# schematic_diagram.net
KiCad netlist of a schematic drawn in EasyEDA
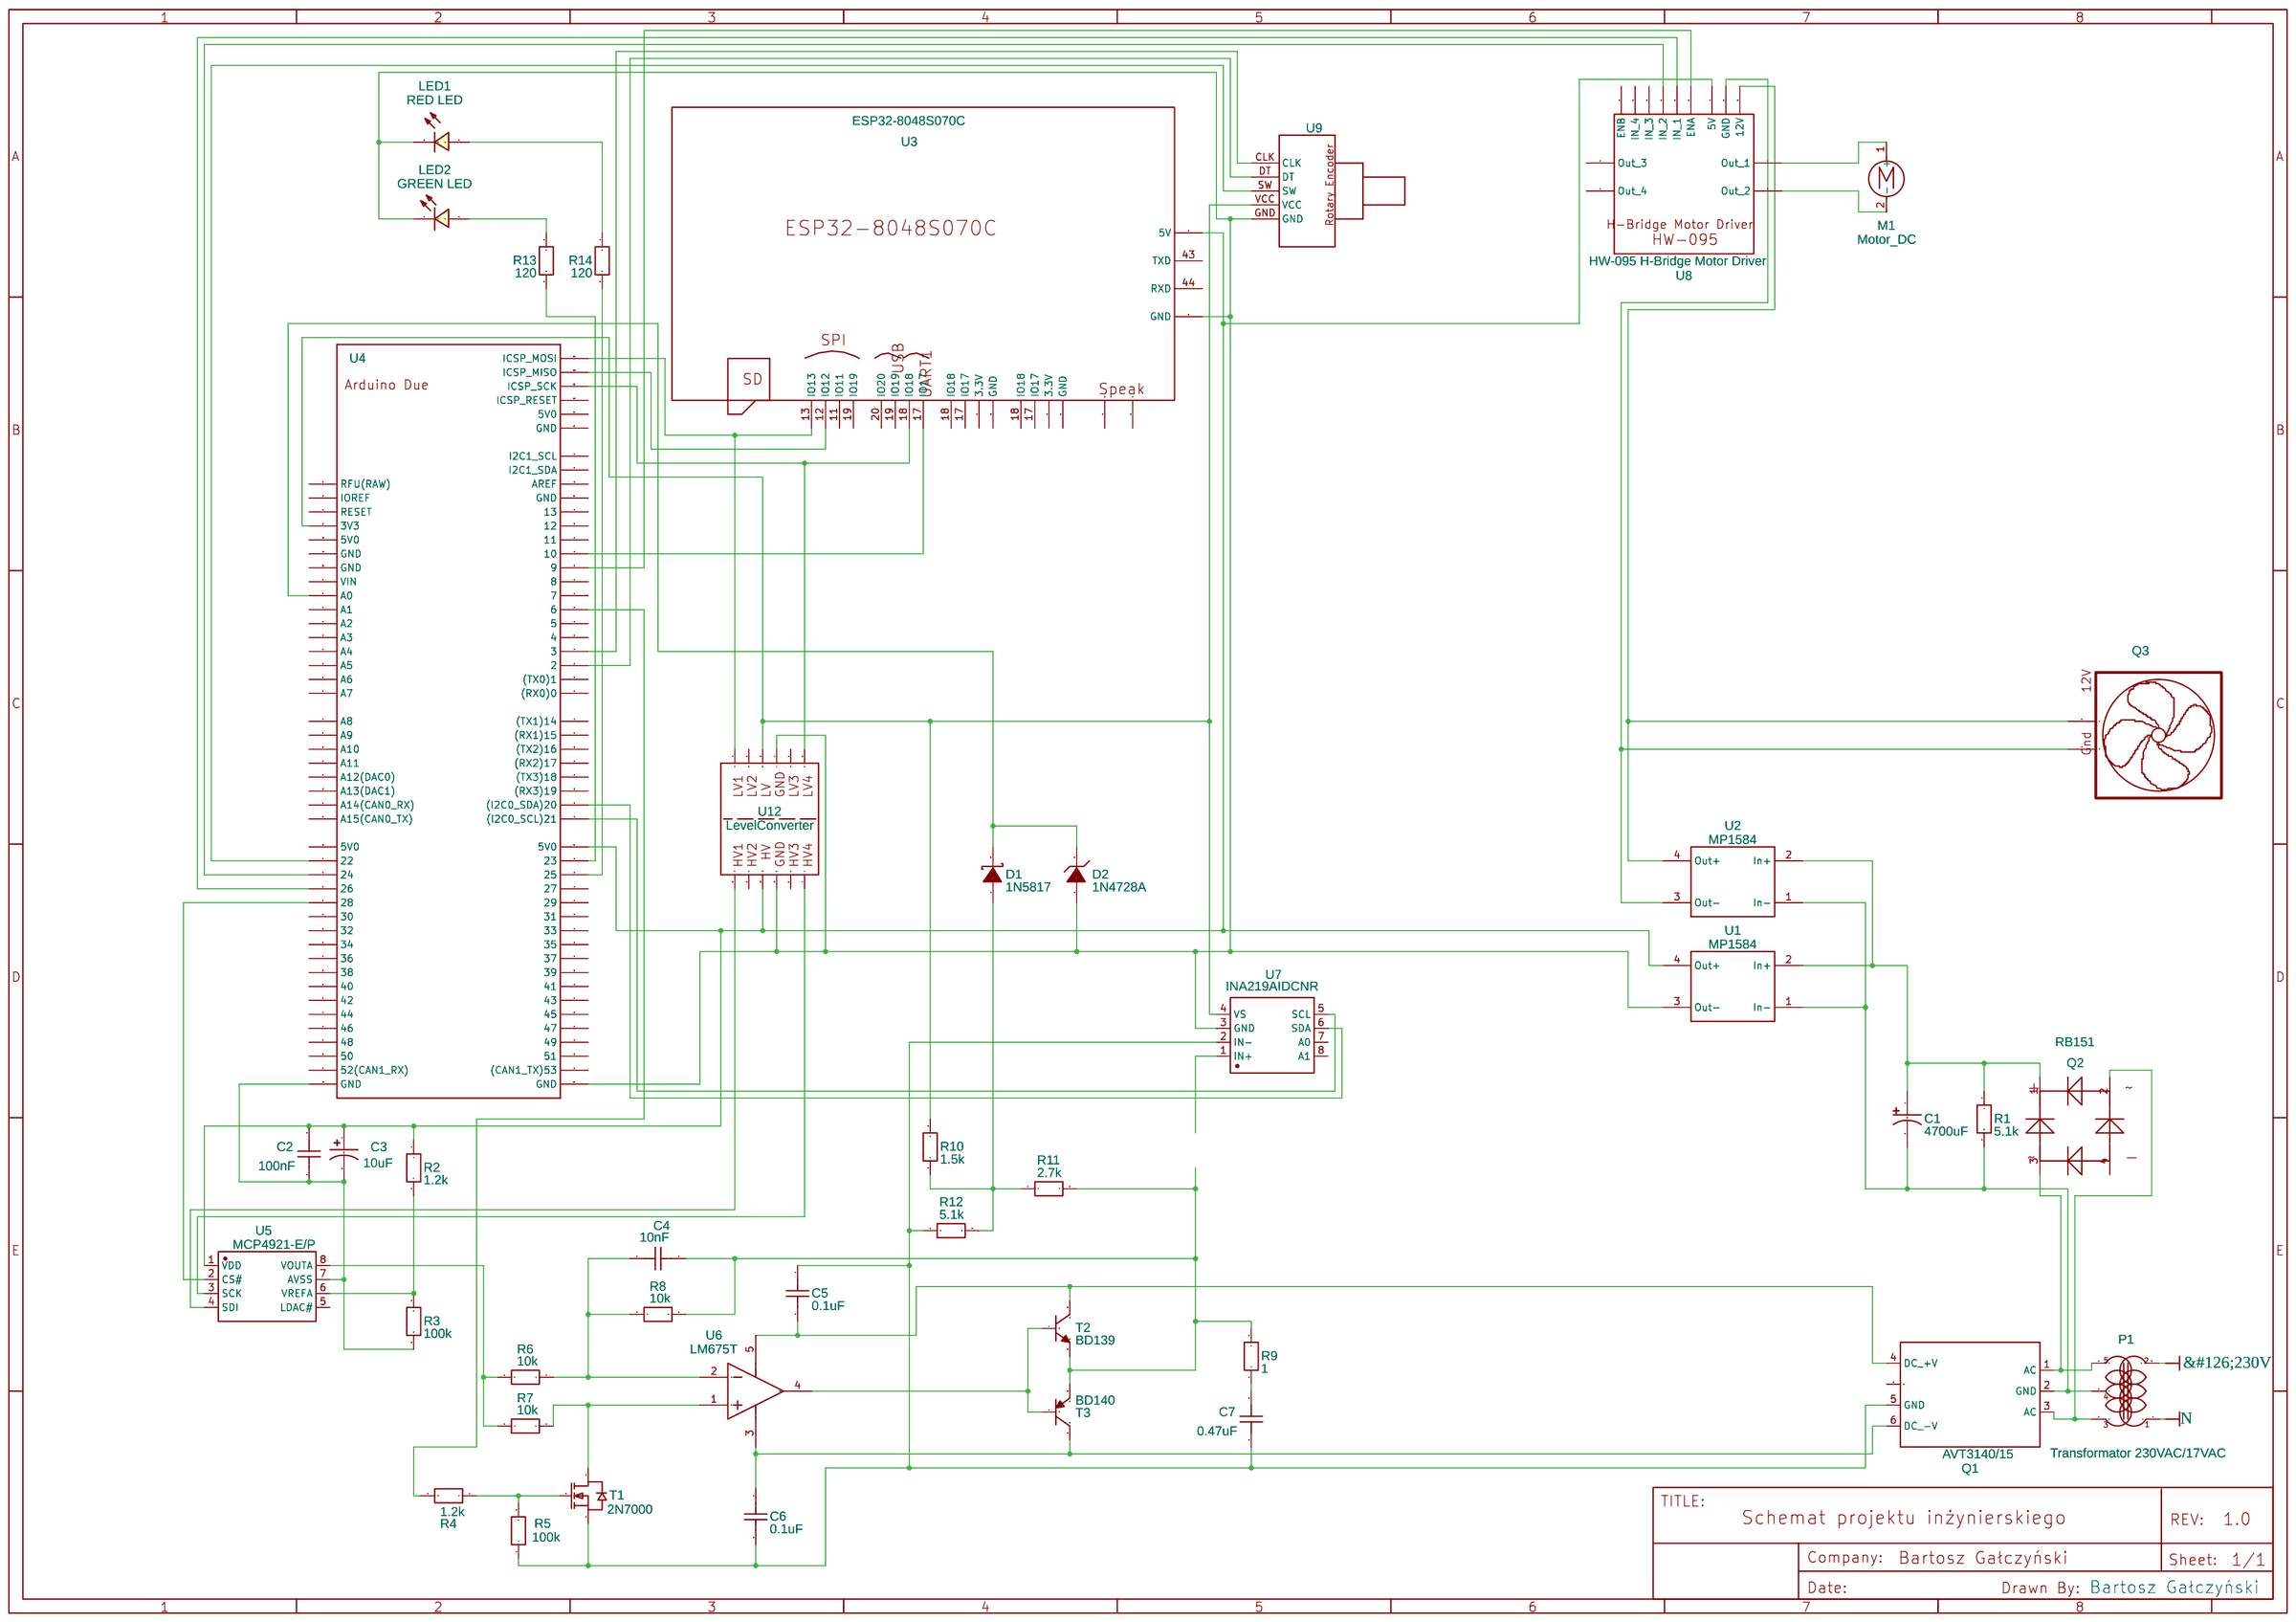
[diagram p0: schematic sheet]

(export (version "E")
  (design (tool "Eeschema 10.0.6"))
  (components
    (comp (ref "C1")
      (value "4700uF")
      (fields
        (field (name "Manufacturer Part") "50ZLH220MEFC10X16")
        (field (name "Manufacturer") "rubycon(红宝石)")
      )
      (libsource (lib "") (part "50ZLH220MEFC10X16"))
    )
    (comp (ref "C2") (value "100nF") (libsource (lib "") (part "C_0603_US_1")))
    (comp (ref "C3") (value "10uF") (libsource (lib "") (part "C_Tan_SMD_A_US")))
    (comp (ref "C4") (value "10nF") (libsource (lib "") (part "C_0603_US")))
    (comp (ref "C5") (value "0.1uF") (libsource (lib "") (part "C_0603_US_2")))
    (comp (ref "C6") (value "0.1uF") (libsource (lib "") (part "C_0603_US_2")))
    (comp (ref "C7") (value "0.47uF") (libsource (lib "") (part "C_0603_US_1")))
    (comp (ref "D1")
      (value "1N5817")
      (fields (field (name "Manufacturer") "MDD(辰达半导体)"))
      (libsource (lib "") (part "1N5817"))
    )
    (comp (ref "D2")
      (value "1N4728A")
      (fields (field (name "Manufacturer Part") "1N4733A") (field (name "Manufacturer") "TC(德昌)"))
      (libsource (lib "") (part "1N4733A"))
    )
    (comp (ref "LED1")
      (value "RED LED")
      (fields (field (name "Manufacturer Part") "LED05-红灯"))
      (libsource (lib "") (part "LED"))
    )
    (comp (ref "LED2")
      (value "GREEN LED")
      (fields (field (name "Manufacturer Part") "BLUEled-0603"))
      (libsource (lib "") (part "GREENLED-0603"))
    )
    (comp (ref "M1") (value "Motor_DC") (libsource (lib "") (part "Motor_DC")))
    (comp (ref "P1")
      (value "Transformator 230VAC/17VAC")
      (fields (field (name "Manufacturer Part") "Transformers"))
      (libsource (lib "") (part "TRANS_TOROIDE_40_20"))
    )
    (comp (ref "Q1")
      (value "AVT3140/15")
      (fields (field (name "Manufacturer Part") "SI7949DP-T1-GE3") (field (name "Manufacturer") "VISHAY(威世)"))
      (libsource (lib "") (part "POWER SUPPLY"))
    )
    (comp (ref "Q2")
      (value "RB151")
      (fields (field (name "Manufacturer Part") "RB151 THRU RB157"))
      (libsource (lib "") (part "SILICON BRIDGE RECTIFIER"))
    )
    (comp (ref "Q3") (value "NO") (libsource (lib "") (part "Fan12V")))
    (comp (ref "R1") (value "5.1k") (libsource (lib "") (part "R_0603_EU")))
    (comp (ref "R2") (value "1.2k") (libsource (lib "") (part "R_0603_EU")))
    (comp (ref "R3") (value "100k") (libsource (lib "") (part "R_0603_EU")))
    (comp (ref "R4") (value "1.2k") (libsource (lib "") (part "R_0603_EU_1")))
    (comp (ref "R5") (value "100k") (libsource (lib "") (part "R_0603_EU_3")))
    (comp (ref "R6") (value "10k") (libsource (lib "") (part "R_0603_EU_1")))
    (comp (ref "R7") (value "10k") (libsource (lib "") (part "R_0603_EU_1")))
    (comp (ref "R8") (value "10k") (libsource (lib "") (part "R_0603_EU_1")))
    (comp (ref "R9") (value "1") (libsource (lib "") (part "R_0603_EU")))
    (comp (ref "R10") (value "1.5k") (libsource (lib "") (part "R_0603_EU")))
    (comp (ref "R11") (value "2.7k") (libsource (lib "") (part "R_0603_EU_2")))
    (comp (ref "R12") (value "5.1k") (libsource (lib "") (part "R_0603_EU_2")))
    (comp (ref "R13") (value "120") (libsource (lib "") (part "R_0603_EU_3")))
    (comp (ref "R14") (value "120") (libsource (lib "") (part "R_0603_EU")))
    (comp (ref "T1")
      (value "2N7000")
      (fields (field (name "Manufacturer") "CJ(江苏长电/长晶)"))
      (libsource (lib "") (part "2N7000"))
    )
    (comp (ref "T2")
      (value "BD139")
      (fields (field (name "Manufacturer") "ST(意法半导体)"))
      (libsource (lib "") (part "BD139"))
    )
    (comp (ref "T3")
      (value "BD140")
      (fields (field (name "Manufacturer") "ST(意法半导体)"))
      (libsource (lib "") (part "BD140"))
    )
    (comp (ref "U1") (value "MP1584") (libsource (lib "") (part "MP1584")))
    (comp (ref "U2") (value "MP1584") (libsource (lib "") (part "MP1584")))
    (comp (ref "U3") (value "ESP32-8048S070C") (libsource (lib "") (part "ESP32-8048S070C")))
    (comp (ref "U4") (value "PA_DUE_BRD") (libsource (lib "") (part "PA_DUE_BRD")))
    (comp (ref "U5")
      (value "MCP4921-E/P")
      (fields (field (name "Manufacturer") "MICROCHIP(美国微芯)"))
      (libsource (lib "") (part "MCP4921-E/P"))
    )
    (comp (ref "U6")
      (value "LM675T")
      (fields (field (name "Manufacturer") "TI(德州仪器)"))
      (libsource (lib "") (part "LM675T"))
    )
    (comp (ref "U7")
      (value "INA219AIDCNR")
      (fields (field (name "Manufacturer") "TI(德州仪器)"))
      (libsource (lib "") (part "INA219AIDCNR"))
    )
    (comp (ref "U8")
      (value "HW-095 H-Bridge Motor Driver")
      (fields (field (name "Manufacturer Part") "HW-095") (field (name "Manufacturer") "Lafvin"))
      (libsource (lib "") (part "HW-095 H-Bridge Motor Driver"))
    )
    (comp (ref "U9") (value "NO") (libsource (lib "") (part "ROTARYENCODER")))
    (comp (ref "U12") (value "LevelConverter") (libsource (lib "") (part "LevelConverter_4")))
  )
  (nets
    (net (code "1") (name "&#126;230V") (class "Default")
      (node (ref "P1") (pin "2") (pinfunction "2_2") (pintype "unspecified"))
    )
    (net (code "2") (name "N") (class "Default")
      (node (ref "P1") (pin "1") (pinfunction "1_1") (pintype "unspecified"))
    )
    (net (code "3") (name "Net-(C7-Pad2)") (class "Default")
      (node (ref "C7") (pin "2") (pinfunction "2_2") (pintype "unspecified"))
      (node (ref "R9") (pin "2") (pinfunction "2_2") (pintype "unspecified"))
    )
    (net (code "4") (name "Net-(D1-A)") (class "Default")
      (node (ref "D1") (pin "1") (pinfunction "A_1") (pintype "unspecified"))
      (node (ref "R10") (pin "2") (pinfunction "2_2") (pintype "unspecified"))
      (node (ref "R11") (pin "1") (pinfunction "1_1") (pintype "unspecified"))
      (node (ref "R12") (pin "2") (pinfunction "2_2") (pintype "unspecified"))
    )
    (net (code "5") (name "Net-(D1-K)") (class "Default")
      (node (ref "D1") (pin "2") (pinfunction "K_2") (pintype "unspecified"))
      (node (ref "D2") (pin "2") (pinfunction "K_2") (pintype "unspecified"))
      (node (ref "U4") (pin "A0") (pinfunction "A0_A0") (pintype "unspecified"))
    )
    (net (code "6") (name "Net-(D2-A)") (class "Default")
      (node (ref "D2") (pin "1") (pinfunction "A_1") (pintype "unspecified"))
      (node (ref "LED1") (pin "2") (pinfunction "2_2") (pintype "unspecified"))
      (node (ref "LED2") (pin "1") (pinfunction "K_1") (pintype "unspecified"))
      (node (ref "U1") (pin "3") (pinfunction "Out-_3") (pintype "unspecified"))
      (node (ref "U12") (pin "4") (pinfunction "4_4") (pintype "input"))
      (node (ref "U12") (pin "9") (pinfunction "9_9") (pintype "input"))
      (node (ref "U3") (pin "GND") (pinfunction "GND_GND") (pintype "unspecified"))
      (node (ref "U4") (pin "GND@3") (pinfunction "GND_GND@3") (pintype "unspecified"))
      (node (ref "U7") (pin "3") (pinfunction "GND_3") (pintype "unspecified"))
      (node (ref "U9") (pin "GND") (pinfunction "GND_GND") (pintype "bidirectional"))
    )
    (net (code "7") (name "Net-(LED1-Pad1)") (class "Default")
      (node (ref "LED1") (pin "1") (pinfunction "1_1") (pintype "unspecified"))
      (node (ref "R14") (pin "1") (pinfunction "1_1") (pintype "unspecified"))
    )
    (net (code "8") (name "Net-(LED2-A)") (class "Default")
      (node (ref "LED2") (pin "2") (pinfunction "A_2") (pintype "unspecified"))
      (node (ref "R13") (pin "2") (pinfunction "2_2") (pintype "unspecified"))
    )
    (net (code "9") (name "Net-(M1-+)") (class "Default")
      (node (ref "M1") (pin "1") (pinfunction "+_1") (pintype "unspecified"))
      (node (ref "U8") (pin "1") (pinfunction "Out_1_1") (pintype "unspecified"))
    )
    (net (code "10") (name "Net-(M1--)") (class "Default")
      (node (ref "M1") (pin "2") (pinfunction "-_2") (pintype "unspecified"))
      (node (ref "U8") (pin "2") (pinfunction "Out_2_2") (pintype "unspecified"))
    )
    (net (code "11") (name "Net-(P1-Pad3)") (class "Default")
      (node (ref "P1") (pin "3") (pinfunction "3_3") (pintype "unspecified"))
      (node (ref "Q1") (pin "3") (pinfunction "AC_3") (pintype "passive"))
      (node (ref "Q2") (pin "2") (pinfunction "2_2") (pintype "unspecified"))
    )
    (net (code "12") (name "Net-(P1-Pad5)") (class "Default")
      (node (ref "P1") (pin "5") (pinfunction "5_5") (pintype "unspecified"))
      (node (ref "Q1") (pin "1") (pinfunction "AC_1") (pintype "passive"))
      (node (ref "Q2") (pin "3") (pinfunction "3_3") (pintype "unspecified"))
    )
    (net (code "13") (name "Net-(Q1-DC_+V)") (class "Default")
      (node (ref "C5") (pin "2") (pinfunction "2_2") (pintype "unspecified"))
      (node (ref "Q1") (pin "4") (pinfunction "DC_+V_4") (pintype "passive"))
      (node (ref "T2") (pin "2") (pinfunction "C_2") (pintype "unspecified"))
      (node (ref "U6") (pin "5") (pinfunction "VCC_5") (pintype "passive"))
    )
    (net (code "14") (name "Net-(Q1-DC_-V)") (class "Default")
      (node (ref "C6") (pin "1") (pinfunction "1_1") (pintype "unspecified"))
      (node (ref "Q1") (pin "6") (pinfunction "DC_-V_6") (pintype "passive"))
      (node (ref "T3") (pin "2") (pinfunction "C_2") (pintype "unspecified"))
      (node (ref "U6") (pin "3") (pinfunction "VEE_3") (pintype "passive"))
    )
    (net (code "15") (name "Net-(R4-Pad2)") (class "Default")
      (node (ref "R4") (pin "2") (pinfunction "2_2") (pintype "unspecified"))
      (node (ref "U4") (pin "6") (pinfunction "6_6") (pintype "unspecified"))
    )
    (net (code "16") (name "Net-(R13-Pad1)") (class "Default")
      (node (ref "R13") (pin "1") (pinfunction "1_1") (pintype "unspecified"))
      (node (ref "U4") (pin "23") (pinfunction "23_23") (pintype "unspecified"))
    )
    (net (code "17") (name "Net-(R14-Pad2)") (class "Default")
      (node (ref "R14") (pin "2") (pinfunction "2_2") (pintype "unspecified"))
      (node (ref "U4") (pin "25") (pinfunction "25_25") (pintype "unspecified"))
    )
    (net (code "18") (name "Net-(T1-D)") (class "Default")
      (node (ref "R7") (pin "1") (pinfunction "1_1") (pintype "unspecified"))
      (node (ref "T1") (pin "3") (pinfunction "D_3") (pintype "unspecified"))
      (node (ref "U6") (pin "1") (pinfunction "+IN_1") (pintype "unspecified"))
    )
    (net (code "19") (name "Net-(T1-G)") (class "Default")
      (node (ref "R4") (pin "1") (pinfunction "1_1") (pintype "unspecified"))
      (node (ref "R5") (pin "2") (pinfunction "2_2") (pintype "unspecified"))
      (node (ref "T1") (pin "2") (pinfunction "G_2") (pintype "unspecified"))
    )
    (net (code "20") (name "Net-(T1-S)") (class "Default")
      (node (ref "C5") (pin "1") (pinfunction "1_1") (pintype "unspecified"))
      (node (ref "C6") (pin "2") (pinfunction "2_2") (pintype "unspecified"))
      (node (ref "C7") (pin "1") (pinfunction "1_1") (pintype "unspecified"))
      (node (ref "Q1") (pin "5") (pinfunction "GND_5") (pintype "passive"))
      (node (ref "R12") (pin "1") (pinfunction "1_1") (pintype "unspecified"))
      (node (ref "R5") (pin "1") (pinfunction "1_1") (pintype "unspecified"))
      (node (ref "T1") (pin "1") (pinfunction "S_1") (pintype "unspecified"))
      (node (ref "U7") (pin "2") (pinfunction "IN-_2") (pintype "unspecified"))
    )
    (net (code "21") (name "Net-(T2-B)") (class "Default")
      (node (ref "T2") (pin "1") (pinfunction "B_1") (pintype "unspecified"))
      (node (ref "T3") (pin "1") (pinfunction "B_1") (pintype "unspecified"))
      (node (ref "U6") (pin "4") (pinfunction "OUT_4") (pintype "output"))
    )
    (net (code "22") (name "Net-(T2-E)") (class "Default")
      (node (ref "C4") (pin "2") (pinfunction "2_2") (pintype "unspecified"))
      (node (ref "R11") (pin "2") (pinfunction "2_2") (pintype "unspecified"))
      (node (ref "R8") (pin "1") (pinfunction "1_1") (pintype "unspecified"))
      (node (ref "R9") (pin "1") (pinfunction "1_1") (pintype "unspecified"))
      (node (ref "T2") (pin "3") (pinfunction "E_3") (pintype "unspecified"))
      (node (ref "T3") (pin "3") (pinfunction "E_3") (pintype "unspecified"))
    )
    (net (code "23") (name "Net-(U1-In+)") (class "Default")
      (node (ref "C1") (pin "1") (pinfunction "1_1") (pintype "unspecified"))
      (node (ref "Q2") (pin "1") (pinfunction "1_1") (pintype "unspecified"))
      (node (ref "R1") (pin "1") (pinfunction "1_1") (pintype "unspecified"))
      (node (ref "U1") (pin "2") (pinfunction "In+_2") (pintype "unspecified"))
      (node (ref "U2") (pin "2") (pinfunction "In+_2") (pintype "unspecified"))
    )
    (net (code "24") (name "Net-(U1-In-)") (class "Default")
      (node (ref "C1") (pin "2") (pinfunction "2_2") (pintype "unspecified"))
      (node (ref "P1") (pin "4") (pinfunction "4_4") (pintype "unspecified"))
      (node (ref "Q1") (pin "2") (pinfunction "GND_2") (pintype "passive"))
      (node (ref "R1") (pin "2") (pinfunction "2_2") (pintype "unspecified"))
      (node (ref "U1") (pin "1") (pinfunction "In-_1") (pintype "unspecified"))
      (node (ref "U2") (pin "1") (pinfunction "In-_1") (pintype "unspecified"))
    )
    (net (code "25") (name "Net-(U1-Out+)") (class "Default")
      (node (ref "C2") (pin "2") (pinfunction "2_2") (pintype "unspecified"))
      (node (ref "C3") (pin "1") (pinfunction "1_1") (pintype "unspecified"))
      (node (ref "R2") (pin "1") (pinfunction "1_1") (pintype "unspecified"))
      (node (ref "U1") (pin "4") (pinfunction "Out+_4") (pintype "unspecified"))
      (node (ref "U12") (pin "10") (pinfunction "10_10") (pintype "input"))
      (node (ref "U3") (pin "5V") (pinfunction "5V_5V") (pintype "unspecified"))
      (node (ref "U4") (pin "5V0@1") (pinfunction "5V0_5V0@1") (pintype "unspecified"))
      (node (ref "U5") (pin "1") (pinfunction "VDD_1") (pintype "unspecified"))
      (node (ref "U8") (pin "7") (pinfunction "5V_7") (pintype "unspecified"))
    )
    (net (code "26") (name "Net-(U2-Out+)") (class "Default")
      (node (ref "Q3") (pin "1") (pinfunction "1_1") (pintype "unspecified"))
      (node (ref "U2") (pin "4") (pinfunction "Out+_4") (pintype "unspecified"))
      (node (ref "U8") (pin "5") (pinfunction "12V_5") (pintype "unspecified"))
    )
    (net (code "27") (name "Net-(U2-Out-)") (class "Default")
      (node (ref "Q3") (pin "2") (pinfunction "2_2") (pintype "unspecified"))
      (node (ref "U2") (pin "3") (pinfunction "Out-_3") (pintype "unspecified"))
      (node (ref "U8") (pin "6") (pinfunction "GND_6") (pintype "unspecified"))
    )
    (net (code "28") (name "Net-(U3-IO12)") (class "Default")
      (node (ref "U3") (pin "12") (pinfunction "IO12_12") (pintype "unspecified"))
      (node (ref "U4") (pin "ICSP_MISO") (pinfunction "ICSP_MISO_ICSP_MISO") (pintype "unspecified"))
    )
    (net (code "29") (name "Net-(U3-IO13)") (class "Default")
      (node (ref "U12") (pin "1") (pinfunction "1_1") (pintype "input"))
      (node (ref "U3") (pin "13") (pinfunction "IO13_13") (pintype "unspecified"))
      (node (ref "U4") (pin "ICSP_MOSI") (pinfunction "ICSP_MOSI_ICSP_MOSI") (pintype "unspecified"))
    )
    (net (code "30") (name "Net-(U3-IO17)_1") (class "Default")
      (node (ref "U3") (pin "17") (pinfunction "IO17_17") (pintype "unspecified"))
      (node (ref "U4") (pin "10") (pinfunction "10_10") (pintype "unspecified"))
    )
    (net (code "31") (name "Net-(U3-IO18)_1") (class "Default")
      (node (ref "U12") (pin "6") (pinfunction "6_6") (pintype "input"))
      (node (ref "U3") (pin "18") (pinfunction "IO18_18") (pintype "unspecified"))
      (node (ref "U4") (pin "ICSP_SCK") (pinfunction "ICSP_SCK_ICSP_SCK") (pintype "unspecified"))
    )
    (net (code "32") (name "Net-(U4-(I2C0_SCL)21)") (class "Default")
      (node (ref "U4") (pin "21") (pinfunction "(I2C0_SCL)21_21") (pintype "unspecified"))
      (node (ref "U7") (pin "5") (pinfunction "SCL_5") (pintype "unspecified"))
    )
    (net (code "33") (name "Net-(U4-(I2C0_SDA)20)") (class "Default")
      (node (ref "U4") (pin "20") (pinfunction "(I2C0_SDA)20_20") (pintype "unspecified"))
      (node (ref "U7") (pin "6") (pinfunction "SDA_6") (pintype "unspecified"))
    )
    (net (code "34") (name "Net-(U4-Pad2)") (class "Default")
      (node (ref "U4") (pin "2") (pinfunction "2_2") (pintype "unspecified"))
      (node (ref "U9") (pin "DT") (pinfunction "DT_DT") (pintype "bidirectional"))
    )
    (net (code "35") (name "Net-(U4-Pad3)") (class "Default")
      (node (ref "U4") (pin "3") (pinfunction "3_3") (pintype "unspecified"))
      (node (ref "U9") (pin "CLK") (pinfunction "CLK_CLK") (pintype "bidirectional"))
    )
    (net (code "36") (name "Net-(U4-Pad22)") (class "Default")
      (node (ref "U4") (pin "22") (pinfunction "22_22") (pintype "unspecified"))
      (node (ref "U9") (pin "SW") (pinfunction "SW_SW") (pintype "bidirectional"))
    )
    (net (code "37") (name "Net-(U5-AVSS)") (class "Default")
      (node (ref "C2") (pin "1") (pinfunction "1_1") (pintype "unspecified"))
      (node (ref "C3") (pin "2") (pinfunction "2_2") (pintype "unspecified"))
      (node (ref "R3") (pin "2") (pinfunction "2_2") (pintype "unspecified"))
      (node (ref "U4") (pin "GND@2") (pinfunction "GND_GND@2") (pintype "unspecified"))
      (node (ref "U5") (pin "7") (pinfunction "AVSS_7") (pintype "unspecified"))
    )
    (net (code "38") (name "Net-(U5-CS#)") (class "Default")
      (node (ref "U4") (pin "28") (pinfunction "28_28") (pintype "unspecified"))
      (node (ref "U5") (pin "2") (pinfunction "CS#_2") (pintype "unspecified"))
    )
    (net (code "39") (name "Net-(U5-SCK)") (class "Default")
      (node (ref "U12") (pin "7") (pinfunction "7_7") (pintype "input"))
      (node (ref "U5") (pin "3") (pinfunction "SCK_3") (pintype "unspecified"))
    )
    (net (code "40") (name "Net-(U5-SDI)") (class "Default")
      (node (ref "U12") (pin "12") (pinfunction "12_12") (pintype "input"))
      (node (ref "U5") (pin "4") (pinfunction "SDI_4") (pintype "unspecified"))
    )
    (net (code "41") (name "Net-(U5-VOUTA)") (class "Default")
      (node (ref "R6") (pin "2") (pinfunction "2_2") (pintype "unspecified"))
      (node (ref "R7") (pin "2") (pinfunction "2_2") (pintype "unspecified"))
      (node (ref "U5") (pin "8") (pinfunction "VOUTA_8") (pintype "unspecified"))
    )
    (net (code "42") (name "Net-(U5-VREFA)") (class "Default")
      (node (ref "R2") (pin "2") (pinfunction "2_2") (pintype "unspecified"))
      (node (ref "R3") (pin "1") (pinfunction "1_1") (pintype "unspecified"))
      (node (ref "U5") (pin "6") (pinfunction "VREFA_6") (pintype "unspecified"))
    )
    (net (code "43") (name "Net-(U6--IN)") (class "Default")
      (node (ref "C4") (pin "1") (pinfunction "1_1") (pintype "unspecified"))
      (node (ref "R6") (pin "1") (pinfunction "1_1") (pintype "unspecified"))
      (node (ref "R8") (pin "2") (pinfunction "2_2") (pintype "unspecified"))
      (node (ref "U6") (pin "2") (pinfunction "-IN_2") (pintype "unspecified"))
    )
    (net (code "44") (name "Net-(U7-VS)") (class "Default")
      (node (ref "R10") (pin "1") (pinfunction "1_1") (pintype "unspecified"))
      (node (ref "U12") (pin "3") (pinfunction "3_3") (pintype "input"))
      (node (ref "U4") (pin "3V3") (pinfunction "3V3_3V3") (pintype "unspecified"))
      (node (ref "U7") (pin "4") (pinfunction "VS_4") (pintype "unspecified"))
      (node (ref "U9") (pin "VCC") (pinfunction "VCC_VCC") (pintype "bidirectional"))
    )
    (net (code "45") (name "Net-(U8-ENA)") (class "Default")
      (node (ref "U4") (pin "9") (pinfunction "9_9") (pintype "unspecified"))
      (node (ref "U8") (pin "8") (pinfunction "ENA_8") (pintype "unspecified"))
    )
    (net (code "46") (name "Net-(U8-IN_1)") (class "Default")
      (node (ref "U4") (pin "26") (pinfunction "26_26") (pintype "unspecified"))
      (node (ref "U8") (pin "9") (pinfunction "IN_1_9") (pintype "unspecified"))
    )
    (net (code "47") (name "Net-(U8-IN_2)") (class "Default")
      (node (ref "U4") (pin "24") (pinfunction "24_24") (pintype "unspecified"))
      (node (ref "U8") (pin "10") (pinfunction "IN_2_10") (pintype "unspecified"))
    )
    (net (code "48") (name "unconnected-(Q1-GND-Pad5)") (class "Default")
      (node (ref "Q1") (pin "5") (pinfunction "GND_5") (pintype "unspecified"))
    )
    (net (code "49") (name "unconnected-(Q2-Pad4)") (class "Default")
      (node (ref "Q2") (pin "4") (pinfunction "4_4") (pintype "unspecified"))
    )
    (net (code "50") (name "unconnected-(U3-5V-Pad5)") (class "Default")
      (node (ref "U3") (pin "5") (pinfunction "5V_5") (pintype "unspecified"))
    )
    (net (code "51") (name "unconnected-(U3-IO11-Pad11)") (class "Default")
      (node (ref "U3") (pin "11") (pinfunction "IO11_11") (pintype "unspecified"))
    )
    (net (code "52") (name "unconnected-(U3-IO17-Pad17)") (class "Default")
      (node (ref "U3") (pin "17") (pinfunction "IO17_17") (pintype "unspecified"))
    )
    (net (code "53") (name "unconnected-(U3-IO17-Pad17)_2") (class "Default")
      (node (ref "U3") (pin "17") (pinfunction "IO17_17") (pintype "unspecified"))
    )
    (net (code "54") (name "unconnected-(U3-IO18-Pad18)") (class "Default")
      (node (ref "U3") (pin "18") (pinfunction "IO18_18") (pintype "unspecified"))
    )
    (net (code "55") (name "unconnected-(U3-IO18-Pad18)_2") (class "Default")
      (node (ref "U3") (pin "18") (pinfunction "IO18_18") (pintype "unspecified"))
    )
    (net (code "56") (name "unconnected-(U3-IO19-Pad19)") (class "Default")
      (node (ref "U3") (pin "19") (pinfunction "IO19_19") (pintype "unspecified"))
    )
    (net (code "57") (name "unconnected-(U3-IO19-Pad19)_1") (class "Default")
      (node (ref "U3") (pin "19") (pinfunction "IO19_19") (pintype "unspecified"))
    )
    (net (code "58") (name "unconnected-(U3-IO20-Pad20)") (class "Default")
      (node (ref "U3") (pin "20") (pinfunction "IO20_20") (pintype "unspecified"))
    )
    (net (code "59") (name "unconnected-(U3-Pad3.3V)") (class "Default")
      (node (ref "U3") (pin "3.3V") (pinfunction "3.3V_3.3V") (pintype "unspecified"))
    )
    (net (code "60") (name "unconnected-(U3-Pad3.3V)_1") (class "Default")
      (node (ref "U3") (pin "3.3V") (pinfunction "3.3V_3.3V") (pintype "unspecified"))
    )
    (net (code "61") (name "unconnected-(U3-PadGND)") (class "Default")
      (node (ref "U3") (pin "GND") (pinfunction "GND_GND") (pintype "unspecified"))
    )
    (net (code "62") (name "unconnected-(U3-PadGND)_1") (class "Default")
      (node (ref "U3") (pin "GND") (pinfunction "GND_GND") (pintype "unspecified"))
    )
    (net (code "63") (name "unconnected-(U3-RXD-Pad44)") (class "Default")
      (node (ref "U3") (pin "44") (pinfunction "RXD_44") (pintype "unspecified"))
    )
    (net (code "64") (name "unconnected-(U3-TXD-Pad6)") (class "Default")
      (node (ref "U3") (pin "6") (pinfunction "TXD_6") (pintype "unspecified"))
    )
    (net (code "65") (name "unconnected-(U3-TXD-Pad43)") (class "Default")
      (node (ref "U3") (pin "43") (pinfunction "TXD_43") (pintype "unspecified"))
    )
    (net (code "66") (name "unconnected-(U4-(CAN1_TX)53-Pad53)") (class "Default")
      (node (ref "U4") (pin "53") (pinfunction "(CAN1_TX)53_53") (pintype "unspecified"))
    )
    (net (code "67") (name "unconnected-(U4-(RX0)0-Pad0)") (class "Default")
      (node (ref "U4") (pin "0") (pinfunction "(RX0)0_0") (pintype "unspecified"))
    )
    (net (code "68") (name "unconnected-(U4-(RX1)15-Pad15)") (class "Default")
      (node (ref "U4") (pin "15") (pinfunction "(RX1)15_15") (pintype "unspecified"))
    )
    (net (code "69") (name "unconnected-(U4-(RX2)17-Pad17)") (class "Default")
      (node (ref "U4") (pin "17") (pinfunction "(RX2)17_17") (pintype "unspecified"))
    )
    (net (code "70") (name "unconnected-(U4-(RX3)19-Pad19)") (class "Default")
      (node (ref "U4") (pin "19") (pinfunction "(RX3)19_19") (pintype "unspecified"))
    )
    (net (code "71") (name "unconnected-(U4-(TX0)1-Pad1)") (class "Default")
      (node (ref "U4") (pin "1") (pinfunction "(TX0)1_1") (pintype "unspecified"))
    )
    (net (code "72") (name "unconnected-(U4-(TX1)14-Pad14)") (class "Default")
      (node (ref "U4") (pin "14") (pinfunction "(TX1)14_14") (pintype "unspecified"))
    )
    (net (code "73") (name "unconnected-(U4-(TX2)16-Pad16)") (class "Default")
      (node (ref "U4") (pin "16") (pinfunction "(TX2)16_16") (pintype "unspecified"))
    )
    (net (code "74") (name "unconnected-(U4-(TX3)18-Pad18)") (class "Default")
      (node (ref "U4") (pin "18") (pinfunction "(TX3)18_18") (pintype "unspecified"))
    )
    (net (code "75") (name "unconnected-(U4-5V0-Pad5V0@0)") (class "Default")
      (node (ref "U4") (pin "5V0@0") (pinfunction "5V0_5V0@0") (pintype "unspecified"))
    )
    (net (code "76") (name "unconnected-(U4-5V0-Pad5V0@2)") (class "Default")
      (node (ref "U4") (pin "5V0@2") (pinfunction "5V0_5V0@2") (pintype "unspecified"))
    )
    (net (code "77") (name "unconnected-(U4-5V0-Pad5V0@3)") (class "Default")
      (node (ref "U4") (pin "5V0@3") (pinfunction "5V0_5V0@3") (pintype "passive"))
    )
    (net (code "78") (name "unconnected-(U4-52(CAN1_RX)-Pad52)") (class "Default")
      (node (ref "U4") (pin "52") (pinfunction "52(CAN1_RX)_52") (pintype "unspecified"))
    )
    (net (code "79") (name "unconnected-(U4-A12(DAC0)-PadA12)") (class "Default")
      (node (ref "U4") (pin "A12") (pinfunction "A12(DAC0)_A12") (pintype "unspecified"))
    )
    (net (code "80") (name "unconnected-(U4-A13(DAC1)-PadA13)") (class "Default")
      (node (ref "U4") (pin "A13") (pinfunction "A13(DAC1)_A13") (pintype "unspecified"))
    )
    (net (code "81") (name "unconnected-(U4-A14(CAN0_RX)-PadA14)") (class "Default")
      (node (ref "U4") (pin "A14") (pinfunction "A14(CAN0_RX)_A14") (pintype "unspecified"))
    )
    (net (code "82") (name "unconnected-(U4-A15(CAN0_TX)-PadA15)") (class "Default")
      (node (ref "U4") (pin "A15") (pinfunction "A15(CAN0_TX)_A15") (pintype "unspecified"))
    )
    (net (code "83") (name "unconnected-(U4-GND-PadGND@0)") (class "Default")
      (node (ref "U4") (pin "GND@0") (pinfunction "GND_GND@0") (pintype "unspecified"))
    )
    (net (code "84") (name "unconnected-(U4-GND-PadGND@1)") (class "Default")
      (node (ref "U4") (pin "GND@1") (pinfunction "GND_GND@1") (pintype "unspecified"))
    )
    (net (code "85") (name "unconnected-(U4-GND-PadGND@4)") (class "Default")
      (node (ref "U4") (pin "GND@4") (pinfunction "GND_GND@4") (pintype "unspecified"))
    )
    (net (code "86") (name "unconnected-(U4-GND-PadGND@5)") (class "Default")
      (node (ref "U4") (pin "GND@5") (pinfunction "GND_GND@5") (pintype "passive"))
    )
    (net (code "87") (name "unconnected-(U4-I2C1_SCL-PadSCL1)") (class "Default")
      (node (ref "U4") (pin "SCL1") (pinfunction "I2C1_SCL_SCL1") (pintype "unspecified"))
    )
    (net (code "88") (name "unconnected-(U4-I2C1_SDA-PadSDA1)") (class "Default")
      (node (ref "U4") (pin "SDA1") (pinfunction "I2C1_SDA_SDA1") (pintype "unspecified"))
    )
    (net (code "89") (name "unconnected-(U4-Pad4)") (class "Default")
      (node (ref "U4") (pin "4") (pinfunction "4_4") (pintype "unspecified"))
    )
    (net (code "90") (name "unconnected-(U4-Pad5)") (class "Default")
      (node (ref "U4") (pin "5") (pinfunction "5_5") (pintype "unspecified"))
    )
    (net (code "91") (name "unconnected-(U4-Pad7)") (class "Default")
      (node (ref "U4") (pin "7") (pinfunction "7_7") (pintype "unspecified"))
    )
    (net (code "92") (name "unconnected-(U4-Pad8)") (class "Default")
      (node (ref "U4") (pin "8") (pinfunction "8_8") (pintype "unspecified"))
    )
    (net (code "93") (name "unconnected-(U4-Pad11)") (class "Default")
      (node (ref "U4") (pin "11") (pinfunction "11_11") (pintype "unspecified"))
    )
    (net (code "94") (name "unconnected-(U4-Pad12)") (class "Default")
      (node (ref "U4") (pin "12") (pinfunction "12_12") (pintype "unspecified"))
    )
    (net (code "95") (name "unconnected-(U4-Pad13)") (class "Default")
      (node (ref "U4") (pin "13") (pinfunction "13_13") (pintype "unspecified"))
    )
    (net (code "96") (name "unconnected-(U4-Pad27)") (class "Default")
      (node (ref "U4") (pin "27") (pinfunction "27_27") (pintype "unspecified"))
    )
    (net (code "97") (name "unconnected-(U4-Pad29)") (class "Default")
      (node (ref "U4") (pin "29") (pinfunction "29_29") (pintype "unspecified"))
    )
    (net (code "98") (name "unconnected-(U4-Pad30)") (class "Default")
      (node (ref "U4") (pin "30") (pinfunction "30_30") (pintype "unspecified"))
    )
    (net (code "99") (name "unconnected-(U4-Pad31)") (class "Default")
      (node (ref "U4") (pin "31") (pinfunction "31_31") (pintype "unspecified"))
    )
    (net (code "100") (name "unconnected-(U4-Pad32)") (class "Default")
      (node (ref "U4") (pin "32") (pinfunction "32_32") (pintype "unspecified"))
    )
    (net (code "101") (name "unconnected-(U4-Pad33)") (class "Default")
      (node (ref "U4") (pin "33") (pinfunction "33_33") (pintype "unspecified"))
    )
    (net (code "102") (name "unconnected-(U4-Pad34)") (class "Default")
      (node (ref "U4") (pin "34") (pinfunction "34_34") (pintype "unspecified"))
    )
    (net (code "103") (name "unconnected-(U4-Pad35)") (class "Default")
      (node (ref "U4") (pin "35") (pinfunction "35_35") (pintype "unspecified"))
    )
    (net (code "104") (name "unconnected-(U4-Pad36)") (class "Default")
      (node (ref "U4") (pin "36") (pinfunction "36_36") (pintype "unspecified"))
    )
    (net (code "105") (name "unconnected-(U4-Pad37)") (class "Default")
      (node (ref "U4") (pin "37") (pinfunction "37_37") (pintype "unspecified"))
    )
    (net (code "106") (name "unconnected-(U4-Pad38)") (class "Default")
      (node (ref "U4") (pin "38") (pinfunction "38_38") (pintype "unspecified"))
    )
    (net (code "107") (name "unconnected-(U4-Pad39)") (class "Default")
      (node (ref "U4") (pin "39") (pinfunction "39_39") (pintype "unspecified"))
    )
    (net (code "108") (name "unconnected-(U4-Pad40)") (class "Default")
      (node (ref "U4") (pin "40") (pinfunction "40_40") (pintype "unspecified"))
    )
    (net (code "109") (name "unconnected-(U4-Pad41)") (class "Default")
      (node (ref "U4") (pin "41") (pinfunction "41_41") (pintype "unspecified"))
    )
    (net (code "110") (name "unconnected-(U4-Pad42)") (class "Default")
      (node (ref "U4") (pin "42") (pinfunction "42_42") (pintype "unspecified"))
    )
    (net (code "111") (name "unconnected-(U4-Pad43)") (class "Default")
      (node (ref "U4") (pin "43") (pinfunction "43_43") (pintype "unspecified"))
    )
    (net (code "112") (name "unconnected-(U4-Pad44)") (class "Default")
      (node (ref "U4") (pin "44") (pinfunction "44_44") (pintype "unspecified"))
    )
    (net (code "113") (name "unconnected-(U4-Pad45)") (class "Default")
      (node (ref "U4") (pin "45") (pinfunction "45_45") (pintype "unspecified"))
    )
    (net (code "114") (name "unconnected-(U4-Pad46)") (class "Default")
      (node (ref "U4") (pin "46") (pinfunction "46_46") (pintype "unspecified"))
    )
    (net (code "115") (name "unconnected-(U4-Pad47)") (class "Default")
      (node (ref "U4") (pin "47") (pinfunction "47_47") (pintype "unspecified"))
    )
    (net (code "116") (name "unconnected-(U4-Pad48)") (class "Default")
      (node (ref "U4") (pin "48") (pinfunction "48_48") (pintype "unspecified"))
    )
    (net (code "117") (name "unconnected-(U4-Pad49)") (class "Default")
      (node (ref "U4") (pin "49") (pinfunction "49_49") (pintype "unspecified"))
    )
    (net (code "118") (name "unconnected-(U4-Pad50)") (class "Default")
      (node (ref "U4") (pin "50") (pinfunction "50_50") (pintype "unspecified"))
    )
    (net (code "119") (name "unconnected-(U4-Pad51)") (class "Default")
      (node (ref "U4") (pin "51") (pinfunction "51_51") (pintype "unspecified"))
    )
    (net (code "120") (name "unconnected-(U4-PadA1)") (class "Default")
      (node (ref "U4") (pin "A1") (pinfunction "A1_A1") (pintype "unspecified"))
    )
    (net (code "121") (name "unconnected-(U4-PadA2)") (class "Default")
      (node (ref "U4") (pin "A2") (pinfunction "A2_A2") (pintype "unspecified"))
    )
    (net (code "122") (name "unconnected-(U4-PadA3)") (class "Default")
      (node (ref "U4") (pin "A3") (pinfunction "A3_A3") (pintype "unspecified"))
    )
    (net (code "123") (name "unconnected-(U4-PadA4)") (class "Default")
      (node (ref "U4") (pin "A4") (pinfunction "A4_A4") (pintype "unspecified"))
    )
    (net (code "124") (name "unconnected-(U4-PadA5)") (class "Default")
      (node (ref "U4") (pin "A5") (pinfunction "A5_A5") (pintype "unspecified"))
    )
    (net (code "125") (name "unconnected-(U4-PadA6)") (class "Default")
      (node (ref "U4") (pin "A6") (pinfunction "A6_A6") (pintype "unspecified"))
    )
    (net (code "126") (name "unconnected-(U4-PadA7)") (class "Default")
      (node (ref "U4") (pin "A7") (pinfunction "A7_A7") (pintype "unspecified"))
    )
    (net (code "127") (name "unconnected-(U4-PadA8)") (class "Default")
      (node (ref "U4") (pin "A8") (pinfunction "A8_A8") (pintype "unspecified"))
    )
    (net (code "128") (name "unconnected-(U4-PadA9)") (class "Default")
      (node (ref "U4") (pin "A9") (pinfunction "A9_A9") (pintype "unspecified"))
    )
    (net (code "129") (name "unconnected-(U4-PadA10)") (class "Default")
      (node (ref "U4") (pin "A10") (pinfunction "A10_A10") (pintype "unspecified"))
    )
    (net (code "130") (name "unconnected-(U4-PadA11)") (class "Default")
      (node (ref "U4") (pin "A11") (pinfunction "A11_A11") (pintype "unspecified"))
    )
    (net (code "131") (name "unconnected-(U4-PadAREF)") (class "Default")
      (node (ref "U4") (pin "AREF") (pinfunction "AREF_AREF") (pintype "unspecified"))
    )
    (net (code "132") (name "unconnected-(U4-PadICSP_RESET)") (class "Default")
      (node (ref "U4") (pin "ICSP_RESET") (pinfunction "ICSP_RESET_ICSP_RESET") (pintype "unspecified"))
    )
    (net (code "133") (name "unconnected-(U4-PadIOREF)") (class "Default")
      (node (ref "U4") (pin "IOREF") (pinfunction "IOREF_IOREF") (pintype "output"))
    )
    (net (code "134") (name "unconnected-(U4-PadRESET)") (class "Default")
      (node (ref "U4") (pin "RESET") (pinfunction "RESET_RESET") (pintype "unspecified"))
    )
    (net (code "135") (name "unconnected-(U4-PadVIN)") (class "Default")
      (node (ref "U4") (pin "VIN") (pinfunction "VIN_VIN") (pintype "unspecified"))
    )
    (net (code "136") (name "unconnected-(U4-RFU(RAW)-PadRFU)") (class "Default")
      (node (ref "U4") (pin "RFU") (pinfunction "RFU(RAW)_RFU") (pintype "passive"))
    )
    (net (code "137") (name "unconnected-(U5-LDAC#-Pad5)") (class "Default")
      (node (ref "U5") (pin "5") (pinfunction "LDAC#_5") (pintype "unspecified"))
    )
    (net (code "138") (name "unconnected-(U7-A0-Pad7)") (class "Default")
      (node (ref "U7") (pin "7") (pinfunction "A0_7") (pintype "unspecified"))
    )
    (net (code "139") (name "unconnected-(U7-A1-Pad8)") (class "Default")
      (node (ref "U7") (pin "8") (pinfunction "A1_8") (pintype "unspecified"))
    )
    (net (code "140") (name "unconnected-(U7-IN+-Pad1)") (class "Default")
      (node (ref "U7") (pin "1") (pinfunction "IN+_1") (pintype "unspecified"))
    )
    (net (code "141") (name "unconnected-(U8-ENB-Pad13)") (class "Default")
      (node (ref "U8") (pin "13") (pinfunction "ENB_13") (pintype "unspecified"))
    )
    (net (code "142") (name "unconnected-(U8-IN_3-Pad11)") (class "Default")
      (node (ref "U8") (pin "11") (pinfunction "IN_3_11") (pintype "unspecified"))
    )
    (net (code "143") (name "unconnected-(U8-IN_4-Pad12)") (class "Default")
      (node (ref "U8") (pin "12") (pinfunction "IN_4_12") (pintype "unspecified"))
    )
    (net (code "144") (name "unconnected-(U8-Out_3-Pad3)") (class "Default")
      (node (ref "U8") (pin "3") (pinfunction "Out_3_3") (pintype "unspecified"))
    )
    (net (code "145") (name "unconnected-(U8-Out_4-Pad4)") (class "Default")
      (node (ref "U8") (pin "4") (pinfunction "Out_4_4") (pintype "unspecified"))
    )
    (net (code "146") (name "unconnected-(U12-Pad2)") (class "Default")
      (node (ref "U12") (pin "2") (pinfunction "2_2") (pintype "input"))
    )
    (net (code "147") (name "unconnected-(U12-Pad5)") (class "Default")
      (node (ref "U12") (pin "5") (pinfunction "5_5") (pintype "input"))
    )
    (net (code "148") (name "unconnected-(U12-Pad8)") (class "Default")
      (node (ref "U12") (pin "8") (pinfunction "8_8") (pintype "input"))
    )
    (net (code "149") (name "unconnected-(U12-Pad11)") (class "Default")
      (node (ref "U12") (pin "11") (pinfunction "11_11") (pintype "input"))
    )
  )
)
